# Power.net
KiCad netlist of a schematic drawn in Altium Designer
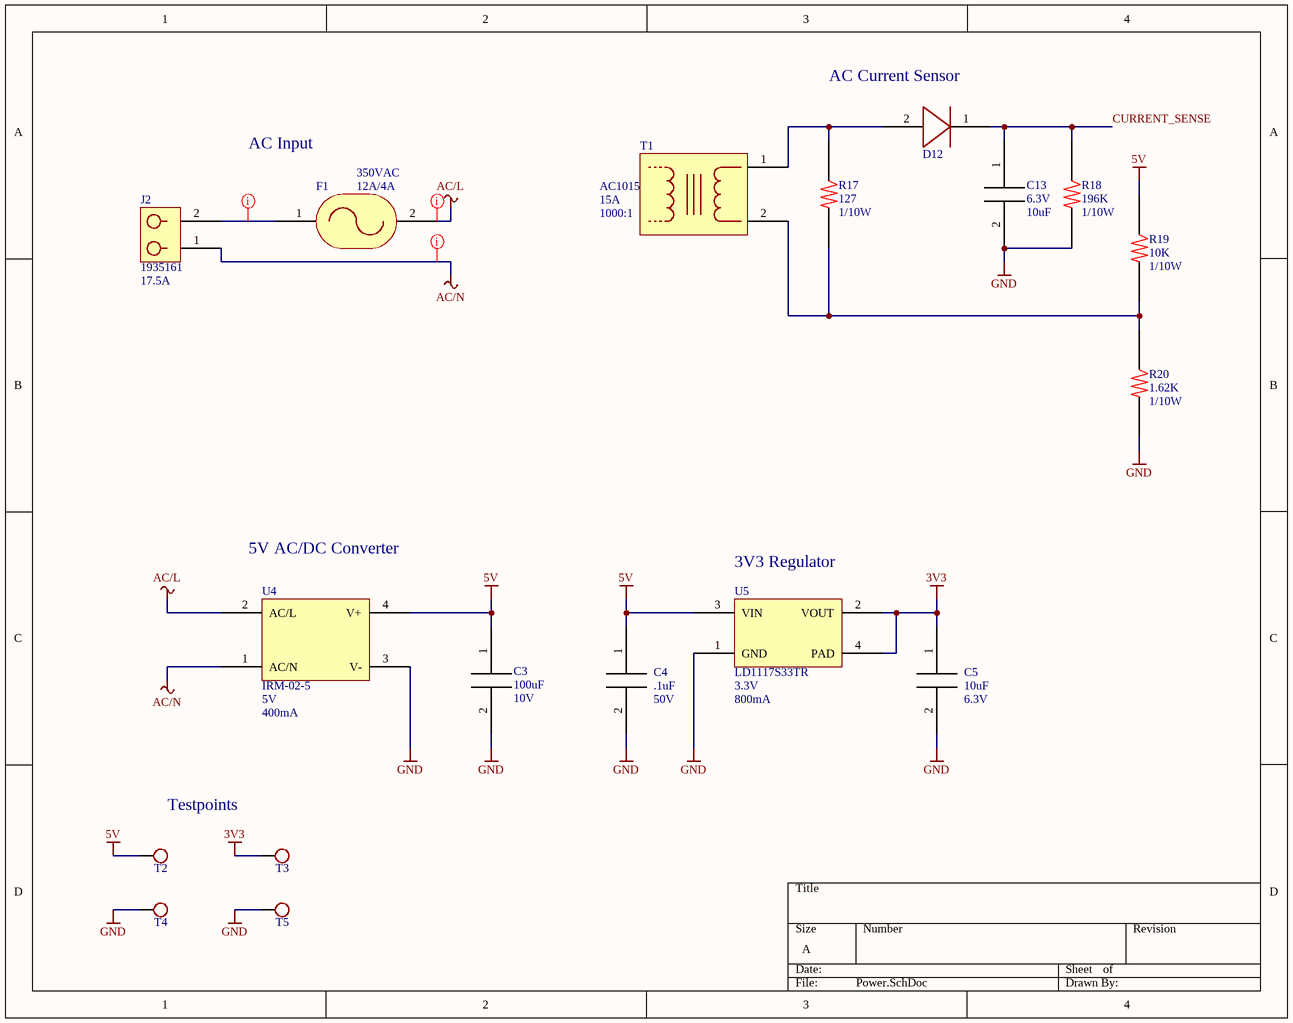
[diagram p0: Power.SchDoc]

(export (version "E")
  (design (tool "Eeschema 10.0.6"))
  (components
    (comp (ref "C3")
      (value "100uF")
      (footprint "1210")
      (fields
        (field (name "PARTNUMBER") "GRM32ER61A107ME20L")
        (field (name "MANUFACTURER") "Murata")
        (field (name "RATING") "10V")
        (field (name "Comment") "C_CAP_1210")
      )
      (libsource (lib "SeniorProject") (part "C_CAP_1210"))
    )
    (comp (ref "C4")
      (value ".1uF")
      (footprint "0603")
      (fields (field (name "RATING") "50V") (field (name "Comment") "C_CAP_0603"))
      (libsource (lib "SeniorProject") (part "C_CAP_0603"))
    )
    (comp (ref "C5")
      (value "10uF")
      (footprint "0603")
      (fields
        (field (name "PARTNUMBER") "JMK107ABJ106MA-T")
        (field (name "MANUFACTURER") "Taiyo Yuden")
        (field (name "RATING") "6.3V")
        (field (name "Comment") "C_CAP_0603")
      )
      (libsource (lib "SeniorProject") (part "C_CAP_0603"))
    )
    (comp (ref "C13")
      (value "10uF")
      (footprint "0603")
      (fields
        (field (name "PARTNUMBER") "JMK107ABJ106MA-T")
        (field (name "MANUFACTURER") "Taiyo Yuden")
        (field (name "RATING") "6.3V")
        (field (name "Comment") "C_CAP_0603")
      )
      (libsource (lib "SeniorProject") (part "C_CAP_0603"))
    )
    (comp (ref "D12")
      (value "D_DIODE_SOD123")
      (footprint "SOD123")
      (fields (field (name "PARTNUMBER") "BAS16GWJ") (field (name "MANUFACTURER") "Nexperia USA Inc"))
      (libsource (lib "SeniorProject") (part "D_DIODE_SOD123"))
    )
    (comp (ref "F1")
      (value "12A/4A")
      (footprint "2410")
      (fields
        (field (name "PARTNUMBER") "0679H9120-05/0679H4000-05")
        (field (name "MANUFACTURER") "Bel Fuse")
        (field (name "RATING") "350VAC")
        (field (name "Comment") "F_FUSE_2410")
      )
      (libsource (lib "SeniorProject") (part "F_FUSE_2410"))
    )
    (comp (ref "J2")
      (value "J_2POSTERM_1935161")
      (footprint "1935161")
      (fields
        (field (name "MANUFACTURER") "Phoenix Contact")
        (field (name "PARTNUMBER") "1935161")
        (field (name "RATING") "17.5A")
      )
      (libsource (lib "SeniorProject") (part "J_2POSTERM_1935161"))
    )
    (comp (ref "R17")
      (value "127")
      (footprint "0603")
      (fields
        (field (name "PARTNUMBER") "RC0603FR-07127RL")
        (field (name "MANUFACTURER") "Yageo")
        (field (name "RATING") "1/10W")
        (field (name "Comment") "R_RES_0603")
      )
      (libsource (lib "SeniorProject") (part "R_RES_0603"))
    )
    (comp (ref "R18")
      (value "196K")
      (footprint "0603")
      (fields
        (field (name "PARTNUMBER") "RC0603FR-07196KL")
        (field (name "MANUFACTURER") "Yageo")
        (field (name "RATING") "1/10W")
        (field (name "Comment") "R_RES_0603")
      )
      (libsource (lib "SeniorProject") (part "R_RES_0603"))
    )
    (comp (ref "R19")
      (value "10K")
      (footprint "0603")
      (fields
        (field (name "PARTNUMBER") "RC0603JR-0710KL")
        (field (name "MANUFACTURER") "Yageo")
        (field (name "RATING") "1/10W")
        (field (name "Comment") "R_RES_0603")
      )
      (libsource (lib "SeniorProject") (part "R_RES_0603"))
    )
    (comp (ref "R20")
      (value "1.62K")
      (footprint "0603")
      (fields
        (field (name "PARTNUMBER") "RC0603FR-071K62L")
        (field (name "MANUFACTURER") "Yageo")
        (field (name "RATING") "1/10W")
        (field (name "Comment") "R_RES_0603")
      )
      (libsource (lib "SeniorProject") (part "R_RES_0603"))
    )
    (comp (ref "T1")
      (value "1000:1")
      (footprint "AC1015")
      (fields
        (field (name "MANUFACTURER") "Acme Electric/Amveco/Actown")
        (field (name "RATING") "15A")
        (field (name "PARTNUMBER") "AC1015")
        (field (name "Comment") "T_CURRTRANS_AC1015")
      )
      (libsource (lib "SeniorProject") (part "T_CURRTRANS_AC1015"))
    )
    (comp (ref "T2")
      (value "TESTPOINT")
      (footprint "TESTPOINT1MM")
      (libsource (lib "SeniorProject") (part "T_TESTPOINT_TESTPOINT1MM"))
    )
    (comp (ref "T3")
      (value "TESTPOINT")
      (footprint "TESTPOINT1MM")
      (libsource (lib "SeniorProject") (part "T_TESTPOINT_TESTPOINT1MM"))
    )
    (comp (ref "T4")
      (value "TESTPOINT")
      (footprint "TESTPOINT1MM")
      (libsource (lib "SeniorProject") (part "T_TESTPOINT_TESTPOINT1MM"))
    )
    (comp (ref "T5")
      (value "TESTPOINT")
      (footprint "TESTPOINT1MM")
      (libsource (lib "SeniorProject") (part "T_TESTPOINT_TESTPOINT1MM"))
    )
    (comp (ref "U4")
      (value "5V")
      (footprint "IRM-02-5")
      (fields
        (field (name "RATING") "400mA")
        (field (name "PARTNUMBER") "IRM-02-5")
        (field (name "Comment") "U_IRM-02-5_IRM-02-5")
      )
      (libsource (lib "SeniorProject") (part "U_IRM-02-5_IRM-02-5"))
    )
    (comp (ref "U5")
      (value "3.3V")
      (footprint "SOT223")
      (fields
        (field (name "RATING") "800mA")
        (field (name "PARTNUMBER") "LD1117S33TR")
        (field (name "Comment") "U_LD1117S33TR_SOT223")
      )
      (libsource (lib "SeniorProject") (part "U_LD1117S33TR_SOT223"))
    )
  )
  (nets
    (net (code "1") (name "/CURRENT_SENSE") (class "Default")
      (node (ref "C13") (pin "1") (pintype "passive"))
      (node (ref "D12") (pin "1") (pintype "passive"))
      (node (ref "R18") (pin "1") (pintype "passive"))
    )
    (net (code "2") (name "3V3") (class "Default")
      (node (ref "C5") (pin "1") (pintype "passive"))
      (node (ref "T3") (pin "1") (pintype "passive"))
      (node (ref "U5") (pin "2") (pinfunction "VOUT_2") (pintype "passive"))
      (node (ref "U5") (pin "4") (pinfunction "PAD_4") (pintype "passive"))
    )
    (net (code "3") (name "5V") (class "Default")
      (node (ref "C3") (pin "1") (pintype "passive"))
      (node (ref "C4") (pin "1") (pintype "passive"))
      (node (ref "R19") (pin "1") (pintype "passive"))
      (node (ref "T2") (pin "1") (pintype "passive"))
      (node (ref "U4") (pin "4") (pinfunction "V+_4") (pintype "passive"))
      (node (ref "U5") (pin "3") (pinfunction "VIN_3") (pintype "power_in"))
    )
    (net (code "4") (name "AC{slash}L") (class "Default")
      (node (ref "F1") (pin "2") (pintype "passive"))
      (node (ref "U4") (pin "2") (pinfunction "AC/L_2") (pintype "passive"))
    )
    (net (code "5") (name "AC{slash}N") (class "Default")
      (node (ref "J2") (pin "1") (pintype "passive"))
      (node (ref "U4") (pin "1") (pinfunction "AC/N_1") (pintype "power_in"))
    )
    (net (code "6") (name "GND") (class "Default")
      (node (ref "C13") (pin "2") (pintype "passive"))
      (node (ref "C3") (pin "2") (pintype "passive"))
      (node (ref "C4") (pin "2") (pintype "passive"))
      (node (ref "C5") (pin "2") (pintype "passive"))
      (node (ref "R18") (pin "2") (pintype "passive"))
      (node (ref "R20") (pin "2") (pintype "passive"))
      (node (ref "T4") (pin "1") (pintype "passive"))
      (node (ref "T5") (pin "1") (pintype "passive"))
      (node (ref "U4") (pin "3") (pinfunction "V-_3") (pintype "passive"))
      (node (ref "U5") (pin "1") (pinfunction "GND_1") (pintype "passive"))
    )
    (net (code "7") (name "Net-(D12-Pad2)") (class "Default")
      (node (ref "D12") (pin "2") (pintype "passive"))
      (node (ref "R17") (pin "1") (pintype "passive"))
      (node (ref "T1") (pin "1") (pintype "passive"))
    )
    (net (code "8") (name "Net-(F1-Pad1)") (class "Default")
      (node (ref "F1") (pin "1") (pintype "passive"))
      (node (ref "J2") (pin "2") (pintype "passive"))
    )
    (net (code "9") (name "Net-(R17-Pad2)") (class "Default")
      (node (ref "R17") (pin "2") (pintype "passive"))
      (node (ref "R19") (pin "2") (pintype "passive"))
      (node (ref "R20") (pin "1") (pintype "passive"))
      (node (ref "T1") (pin "2") (pintype "passive"))
    )
  )
)
